# 3V-Switcher-50mA.net
KiCad netlist of a schematic drawn in Altium Designer
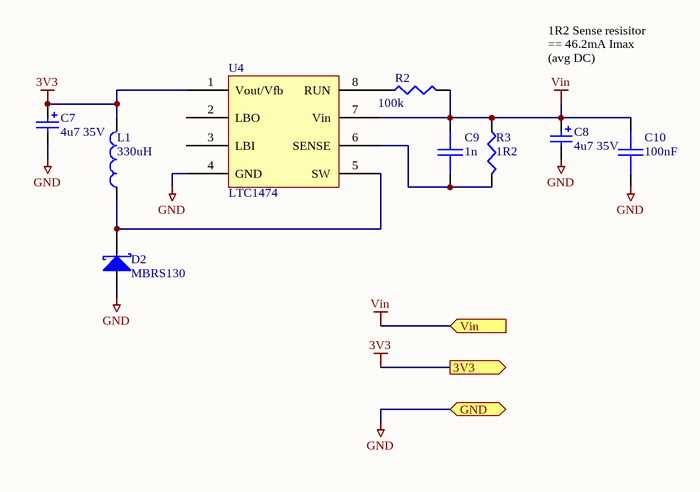
[diagram p0: 3V-Switcher-50mA.SchDoc]

(export (version "E")
  (design (tool "Eeschema 10.0.6"))
  (components
    (comp (ref "C7")
      (value "4u7 35V")
      (footprint "MCCT-CASEC")
      (description "Polarized Capacitor (Surface Mount)")
      (libsource (lib "Miscellaneous Devices") (part "Cap Pol3"))
    )
    (comp (ref "C8")
      (value "4u7 35V")
      (footprint "MCCT-CASEC")
      (description "Polarized Capacitor (Surface Mount)")
      (libsource (lib "Miscellaneous Devices") (part "Cap Pol3"))
    )
    (comp (ref "C9")
      (value "1n")
      (footprint "0603")
      (description "Capacitor")
      (libsource (lib "Miscellaneous Devices") (part "CAP"))
    )
    (comp (ref "C10")
      (value "100nF")
      (footprint "0603")
      (description "Capacitor")
      (libsource (lib "Miscellaneous Devices") (part "CAP"))
    )
    (comp (ref "D2")
      (value "MBRS130")
      (footprint "SMB")
      (description "Schottky Diode")
      (libsource (lib "RCLDQ") (part "D SCHOTTKY"))
    )
    (comp (ref "L1")
      (value "330uH")
      (footprint "1812")
      (description "Inductor")
      (libsource (lib "Miscellaneous Devices") (part "Inductor"))
    )
    (comp (ref "R2")
      (value "100k")
      (footprint "0603")
      (description "Resistor")
      (libsource (lib "RCLDQ") (part "RES1"))
    )
    (comp (ref "R3")
      (value "1R2")
      (footprint "0603")
      (description "Resistor")
      (libsource (lib "Miscellaneous Devices") (part "RES1"))
    )
    (comp (ref "U4")
      (value "LTC1474")
      (footprint "SO8")
      (description "Step-down converter")
      (libsource (lib "MiscellaneousIC") (part "LTC1474"))
    )
  )
  (nets
    (net (code "1") (name "3V3") (class "Default")
      (node (ref "C7") (pin "1") (pinfunction "1_1") (pintype "passive"))
      (node (ref "L1") (pin "2") (pinfunction "2_2") (pintype "passive"))
      (node (ref "U4") (pin "1") (pinfunction "Vout/Vfb_1") (pintype "passive"))
    )
    (net (code "2") (name "GND") (class "Default")
      (node (ref "C10") (pin "2") (pinfunction "2_2") (pintype "passive"))
      (node (ref "C7") (pin "2") (pinfunction "2_2") (pintype "passive"))
      (node (ref "C8") (pin "2") (pinfunction "2_2") (pintype "passive"))
      (node (ref "D2") (pin "A") (pinfunction "A_A") (pintype "passive"))
      (node (ref "U4") (pin "4") (pinfunction "GND_4") (pintype "passive"))
    )
    (net (code "3") (name "Net-(U4-RUN)") (class "Default")
      (node (ref "R2") (pin "1") (pinfunction "1_1") (pintype "passive"))
      (node (ref "U4") (pin "8") (pinfunction "RUN_8") (pintype "passive"))
    )
    (net (code "4") (name "Net-(U4-SENSE)") (class "Default")
      (node (ref "C9") (pin "2") (pinfunction "2_2") (pintype "passive"))
      (node (ref "R3") (pin "2") (pinfunction "2_2") (pintype "passive"))
      (node (ref "U4") (pin "6") (pinfunction "SENSE_6") (pintype "passive"))
    )
    (net (code "5") (name "Net-(U4-SW)") (class "Default")
      (node (ref "D2") (pin "K") (pinfunction "K_K") (pintype "passive"))
      (node (ref "L1") (pin "1") (pinfunction "1_1") (pintype "passive"))
      (node (ref "U4") (pin "5") (pinfunction "SW_5") (pintype "passive"))
    )
    (net (code "6") (name "Vin") (class "Default")
      (node (ref "C10") (pin "1") (pinfunction "1_1") (pintype "passive"))
      (node (ref "C8") (pin "1") (pinfunction "1_1") (pintype "passive"))
      (node (ref "C9") (pin "1") (pinfunction "1_1") (pintype "passive"))
      (node (ref "R2") (pin "2") (pinfunction "2_2") (pintype "passive"))
      (node (ref "R3") (pin "1") (pinfunction "1_1") (pintype "passive"))
      (node (ref "U4") (pin "7") (pinfunction "Vin_7") (pintype "passive"))
    )
    (net (code "7") (name "unconnected-(U4-LBI-Pad3)") (class "Default")
      (node (ref "U4") (pin "3") (pinfunction "LBI_3") (pintype "passive"))
    )
    (net (code "8") (name "unconnected-(U4-LBO-Pad2)") (class "Default")
      (node (ref "U4") (pin "2") (pinfunction "LBO_2") (pintype "passive"))
    )
  )
)
